# Pressure_BMP280.net
KiCad netlist of a schematic drawn in Altium Designer
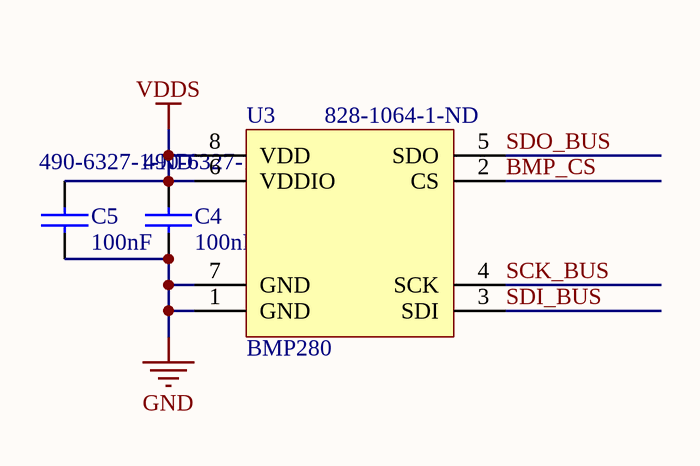
[diagram p0: Pressure_BMP280.SchDoc]

(export (version "E")
  (design (tool "Eeschema 10.0.6"))
  (components
    (comp (ref "C4")
      (value "100nF")
      (footprint "0402[IMP]")
      (fields (field (name "VOLTAGE") "CMAX") (field (name "SUPPLIER PART NUMBER 1") "490-6327-1-ND"))
      (libsource (lib "Biosense_Altium_Library") (part "CAPACITOR"))
    )
    (comp (ref "C5")
      (value "100nF")
      (footprint "0402[IMP]")
      (fields (field (name "VOLTAGE") "CMAX") (field (name "SUPPLIER PART NUMBER 1") "490-6327-1-ND"))
      (libsource (lib "Biosense_Altium_Library") (part "CAPACITOR"))
    )
    (comp (ref "U3")
      (value "BMP280")
      (footprint "LGA-8")
      (fields (field (name "SUPPLIER PART NUMBER 1") "828-1064-1-ND"))
      (libsource (lib "Biosense_Altium_Library") (part "BMP280"))
    )
  )
  (nets
    (net (code "1") (name "/BMP_CS") (class "Default")
      (node (ref "U3") (pin "2") (pinfunction "CS_2") (pintype "passive"))
    )
    (net (code "2") (name "/SCK_BUS") (class "Default")
      (node (ref "U3") (pin "4") (pinfunction "SCK_4") (pintype "passive"))
    )
    (net (code "3") (name "/SDI_BUS") (class "Default")
      (node (ref "U3") (pin "3") (pinfunction "SDI_3") (pintype "passive"))
    )
    (net (code "4") (name "/SDO_BUS") (class "Default")
      (node (ref "U3") (pin "5") (pinfunction "SDO_5") (pintype "passive"))
    )
    (net (code "5") (name "GND") (class "Default")
      (node (ref "C4") (pin "2") (pinfunction "2_2") (pintype "passive"))
      (node (ref "C5") (pin "2") (pinfunction "2_2") (pintype "passive"))
      (node (ref "U3") (pin "1") (pinfunction "GND_1") (pintype "passive"))
      (node (ref "U3") (pin "7") (pinfunction "GND_7") (pintype "passive"))
    )
    (net (code "6") (name "VDDS") (class "Default")
      (node (ref "C4") (pin "1") (pinfunction "1_1") (pintype "passive"))
      (node (ref "C5") (pin "1") (pinfunction "1_1") (pintype "passive"))
      (node (ref "U3") (pin "6") (pinfunction "VDDIO_6") (pintype "passive"))
      (node (ref "U3") (pin "8") (pinfunction "VDD_8") (pintype "passive"))
    )
  )
)
